# POWERSYSTEM.net
KiCad netlist of a schematic drawn in Altium Designer
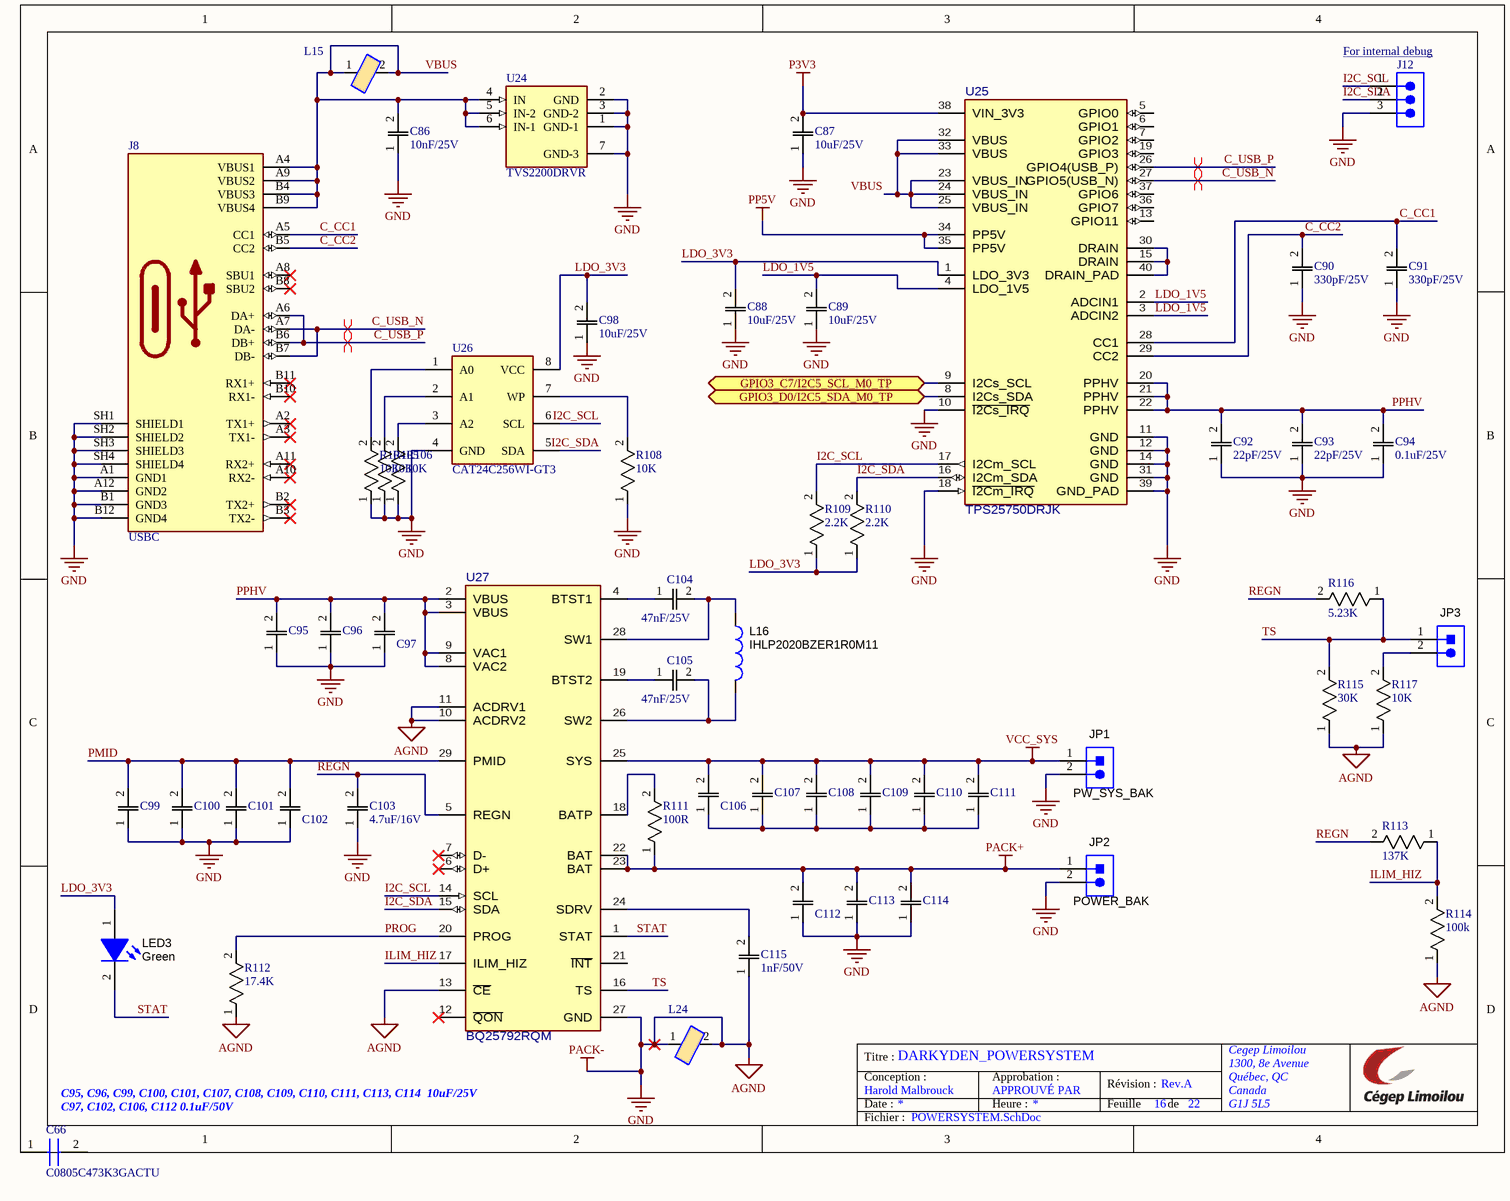
[diagram p0: POWERSYSTEM.SchDoc]

(export (version "E")
  (design (tool "Eeschema 10.0.6"))
  (components
    (comp (ref "C66")
      (value "C0805C473K3GACTU")
      (footprint "SamacSys:C0805")
      (description "Capacitor")
      (fields (field (name "MOUSER PART NUMBER") "80-C0805C473K3G"))
      (libsource (lib "*") (part "C0805C473K3GACTU"))
    )
    (comp (ref "C86")
      (value "10nF/25V")
      (footprint "C0805")
      (description "0.01uF 25V X7R 10% SMD 0805 125C Paper T/R")
      (fields
        (field (name "MANUFACTURER_PART_NUMBER") "C0805C103K3RACTU")
        (field (name "MOUSER PART NUMBER") "80-C0805C103K3R")
      )
      (libsource (lib "DARKYDEN") (part "C0805C103K3RACTU"))
    )
    (comp (ref "C87")
      (value "10uF/25V")
      (footprint "C0805")
      (description "10uF / 25 VDC, +85degC, X5R Dielec, +/-10% ¦ KEMET C0805C106K3PACTU 0805")
      (fields
        (field (name "MANUFACTURER") "KEMET")
        (field (name "MANUFACTURER PART NUMBER") "C0805C106K3PACTU")
      )
      (libsource (lib "DARKYDEN") (part "C0805C106K3PACTU"))
    )
    (comp (ref "C88")
      (value "10uF/25V")
      (footprint "C0805")
      (description "10uF / 25 VDC, +85degC, X5R Dielec, +/-10% ¦ KEMET C0805C106K3PACTU 0805")
      (fields
        (field (name "MANUFACTURER") "KEMET")
        (field (name "MANUFACTURER PART NUMBER") "C0805C106K3PACTU")
      )
      (libsource (lib "DARKYDEN") (part "C0805C106K3PACTU"))
    )
    (comp (ref "C89")
      (value "10uF/25V")
      (footprint "C0805")
      (description "10uF / 25 VDC, +85degC, X5R Dielec, +/-10% ¦ KEMET C0805C106K3PACTU 0805")
      (fields
        (field (name "MANUFACTURER") "KEMET")
        (field (name "MANUFACTURER PART NUMBER") "C0805C106K3PACTU")
      )
      (libsource (lib "DARKYDEN") (part "C0805C106K3PACTU"))
    )
    (comp (ref "C90")
      (value "330pF/25V")
      (footprint "SamacSys:C0805")
      (description "330pF 25VC0G 0805 10%")
      (fields
        (field (name "MANUFACTURER_PART_NUMBER") "C0805C331K3GACTU")
        (field (name "MOUSER PART NUMBER") "80-C0805C331K3G")
      )
      (libsource (lib "DARKYDEN") (part "C0805C331K3GACTU"))
    )
    (comp (ref "C91")
      (value "330pF/25V")
      (footprint "SamacSys:C0805")
      (description "330pF 25VC0G 0805 10%")
      (fields
        (field (name "MANUFACTURER_PART_NUMBER") "C0805C331K3GACTU")
        (field (name "MOUSER PART NUMBER") "80-C0805C331K3G")
      )
      (libsource (lib "DARKYDEN") (part "C0805C331K3GACTU"))
    )
    (comp (ref "C92")
      (value "22pF/25V")
      (footprint "c0805")
      (description "22uF/25V 20% X5R 0805")
      (fields
        (field (name "MANUFACTURER_PART_NUMBER") "CL21A226MAYNNNE")
        (field (name "MOUSER PART NUMBER") "187-CL21A226MAYNNNE")
      )
      (libsource (lib "DARKYDEN") (part "CL21A226MAYNNNE"))
    )
    (comp (ref "C93")
      (value "22pF/25V")
      (footprint "c0805")
      (description "22uF/25V 20% X5R 0805")
      (fields
        (field (name "MANUFACTURER_PART_NUMBER") "CL21A226MAYNNNE")
        (field (name "MOUSER PART NUMBER") "187-CL21A226MAYNNNE")
      )
      (libsource (lib "DARKYDEN") (part "CL21A226MAYNNNE"))
    )
    (comp (ref "C94")
      (value "0.1uF/25V")
      (footprint "c0805")
      (description "0.1uF 25V X7R 10% SMD 0805 125C Plastic T/R")
      (fields
        (field (name "MANUFACTURER") "KEMET")
        (field (name "MANUFACTURER PART NUMBER") "C0805C104K3RACTU")
      )
      (libsource (lib "DARKYDEN") (part "C0805C104K3RACTU"))
    )
    (comp (ref "C95")
      (value "10uF/25V")
      (footprint "C0805")
      (description "10uF / 25 VDC, +85degC, X5R Dielec, +/-10% ¦ KEMET C0805C106K3PACTU 0805")
      (fields
        (field (name "MANUFACTURER") "KEMET")
        (field (name "MANUFACTURER PART NUMBER") "C0805C106K3PACTU")
      )
      (libsource (lib "DARKYDEN") (part "C0805C106K3PACTU"))
    )
    (comp (ref "C96")
      (value "10uF/25V")
      (footprint "C0805")
      (description "10uF / 25 VDC, +85degC, X5R Dielec, +/-10% ¦ KEMET C0805C106K3PACTU 0805")
      (fields
        (field (name "MANUFACTURER") "KEMET")
        (field (name "MANUFACTURER PART NUMBER") "C0805C106K3PACTU")
      )
      (libsource (lib "DARKYDEN") (part "C0805C106K3PACTU"))
    )
    (comp (ref "C97")
      (value "0.1uF/50V")
      (footprint "C0805")
      (description "0.1uF/50V X7R 10% 0805 Multilayer Ceramic Capacitors Mlcc Smd/Smt Rohs")
      (fields
        (field (name "MANUFACTURER_PART_NUMBER") "C0805C104K5RACTU")
        (field (name "MOUSER PART NUMBER") "80-C0805C104K5R")
      )
      (libsource (lib "DARKYDEN") (part "C0805C104K5RACTU"))
    )
    (comp (ref "C98")
      (value "10uF/25V")
      (footprint "C0805")
      (description "10uF / 25 VDC, +85degC, X5R Dielec, +/-10% ¦ KEMET C0805C106K3PACTU 0805")
      (fields
        (field (name "MANUFACTURER") "KEMET")
        (field (name "MANUFACTURER PART NUMBER") "C0805C106K3PACTU")
      )
      (libsource (lib "DARKYDEN") (part "C0805C106K3PACTU"))
    )
    (comp (ref "C99")
      (value "10uF/25V")
      (footprint "C0805")
      (description "10uF / 25 VDC, +85degC, X5R Dielec, +/-10% ¦ KEMET C0805C106K3PACTU 0805")
      (fields
        (field (name "MANUFACTURER") "KEMET")
        (field (name "MANUFACTURER PART NUMBER") "C0805C106K3PACTU")
      )
      (libsource (lib "DARKYDEN") (part "C0805C106K3PACTU"))
    )
    (comp (ref "C100")
      (value "10uF/25V")
      (footprint "C0805")
      (description "10uF / 25 VDC, +85degC, X5R Dielec, +/-10% ¦ KEMET C0805C106K3PACTU 0805")
      (fields
        (field (name "MANUFACTURER") "KEMET")
        (field (name "MANUFACTURER PART NUMBER") "C0805C106K3PACTU")
      )
      (libsource (lib "DARKYDEN") (part "C0805C106K3PACTU"))
    )
    (comp (ref "C101")
      (value "10uF/25V")
      (footprint "C0805")
      (description "10uF / 25 VDC, +85degC, X5R Dielec, +/-10% ¦ KEMET C0805C106K3PACTU 0805")
      (fields
        (field (name "MANUFACTURER") "KEMET")
        (field (name "MANUFACTURER PART NUMBER") "C0805C106K3PACTU")
      )
      (libsource (lib "DARKYDEN") (part "C0805C106K3PACTU"))
    )
    (comp (ref "C102")
      (value "0.1uF/50V")
      (footprint "C0805")
      (description "0.1uF/50V X7R 10% 0805 Multilayer Ceramic Capacitors Mlcc Smd/Smt Rohs")
      (fields
        (field (name "MANUFACTURER_PART_NUMBER") "C0805C104K5RACTU")
        (field (name "MOUSER PART NUMBER") "80-C0805C104K5R")
      )
      (libsource (lib "DARKYDEN") (part "C0805C104K5RACTU"))
    )
    (comp (ref "C103")
      (value "4.7uF/16V")
      (footprint "C0805")
      (description "4.7 uF, 16 V, ± 10%, X7R, 0805 [2012 Metric]")
      (fields
        (field (name "MANUFACTURER_PART_NUMBER") "C0805C475K4RACTU")
        (field (name "MOUSER PART NUMBER") "80-C0805C475K4R")
      )
      (libsource (lib "DARKYDEN") (part "C0805C475K4RACTU"))
    )
    (comp (ref "C104")
      (value "47nF/25V")
      (footprint "C0805")
      (description "47nF/25V C0G 10% Pad SMD 0805 125C Extreme Low ESR T/R")
      (fields
        (field (name "MANUFACTURER_PART_NUMBER") "C0805C473K3GACTU")
        (field (name "MOUSER PART NUMBER") "80-C0805C473K3G")
      )
      (libsource (lib "DARKYDEN") (part "C0805C473K3GACTU"))
    )
    (comp (ref "C105")
      (value "47nF/25V")
      (footprint "C0805")
      (description "47nF/25V C0G 10% Pad SMD 0805 125C Extreme Low ESR T/R")
      (fields
        (field (name "MANUFACTURER_PART_NUMBER") "C0805C473K3GACTU")
        (field (name "MOUSER PART NUMBER") "80-C0805C473K3G")
      )
      (libsource (lib "DARKYDEN") (part "C0805C473K3GACTU"))
    )
    (comp (ref "C106")
      (value "0.1uF/50V")
      (footprint "C0805")
      (description "0.1uF/50V X7R 10% 0805 Multilayer Ceramic Capacitors Mlcc Smd/Smt Rohs")
      (fields
        (field (name "MANUFACTURER_PART_NUMBER") "C0805C104K5RACTU")
        (field (name "MOUSER PART NUMBER") "80-C0805C104K5R")
      )
      (libsource (lib "DARKYDEN") (part "C0805C104K5RACTU"))
    )
    (comp (ref "C107")
      (value "10uF/25V")
      (footprint "C0805")
      (description "10uF / 25 VDC, +85degC, X5R Dielec, +/-10% ¦ KEMET C0805C106K3PACTU 0805")
      (fields
        (field (name "MANUFACTURER") "KEMET")
        (field (name "MANUFACTURER PART NUMBER") "C0805C106K3PACTU")
      )
      (libsource (lib "DARKYDEN") (part "C0805C106K3PACTU"))
    )
    (comp (ref "C108")
      (value "10uF/25V")
      (footprint "C0805")
      (description "10uF / 25 VDC, +85degC, X5R Dielec, +/-10% ¦ KEMET C0805C106K3PACTU 0805")
      (fields
        (field (name "MANUFACTURER") "KEMET")
        (field (name "MANUFACTURER PART NUMBER") "C0805C106K3PACTU")
      )
      (libsource (lib "DARKYDEN") (part "C0805C106K3PACTU"))
    )
    (comp (ref "C109")
      (value "10uF/25V")
      (footprint "C0805")
      (description "10uF / 25 VDC, +85degC, X5R Dielec, +/-10% ¦ KEMET C0805C106K3PACTU 0805")
      (fields
        (field (name "MANUFACTURER") "KEMET")
        (field (name "MANUFACTURER PART NUMBER") "C0805C106K3PACTU")
      )
      (libsource (lib "DARKYDEN") (part "C0805C106K3PACTU"))
    )
    (comp (ref "C110")
      (value "10uF/25V")
      (footprint "C0805")
      (description "10uF / 25 VDC, +85degC, X5R Dielec, +/-10% ¦ KEMET C0805C106K3PACTU 0805")
      (fields
        (field (name "MANUFACTURER") "KEMET")
        (field (name "MANUFACTURER PART NUMBER") "C0805C106K3PACTU")
      )
      (libsource (lib "DARKYDEN") (part "C0805C106K3PACTU"))
    )
    (comp (ref "C111")
      (value "10uF/25V")
      (footprint "C0805")
      (description "10uF / 25 VDC, +85degC, X5R Dielec, +/-10% ¦ KEMET C0805C106K3PACTU 0805")
      (fields
        (field (name "MANUFACTURER") "KEMET")
        (field (name "MANUFACTURER PART NUMBER") "C0805C106K3PACTU")
      )
      (libsource (lib "DARKYDEN") (part "C0805C106K3PACTU"))
    )
    (comp (ref "C112")
      (value "0.1uF/50V")
      (footprint "C0805")
      (description "0.1uF/50V X7R 10% 0805 Multilayer Ceramic Capacitors Mlcc Smd/Smt Rohs")
      (fields
        (field (name "MANUFACTURER_PART_NUMBER") "C0805C104K5RACTU")
        (field (name "MOUSER PART NUMBER") "80-C0805C104K5R")
      )
      (libsource (lib "DARKYDEN") (part "C0805C104K5RACTU"))
    )
    (comp (ref "C113")
      (value "10uF/25V")
      (footprint "C0805")
      (description "10uF / 25 VDC, +85degC, X5R Dielec, +/-10% ¦ KEMET C0805C106K3PACTU 0805")
      (fields
        (field (name "MANUFACTURER") "KEMET")
        (field (name "MANUFACTURER PART NUMBER") "C0805C106K3PACTU")
      )
      (libsource (lib "DARKYDEN") (part "C0805C106K3PACTU"))
    )
    (comp (ref "C114")
      (value "10uF/25V")
      (footprint "C0805")
      (description "10uF / 25 VDC, +85degC, X5R Dielec, +/-10% ¦ KEMET C0805C106K3PACTU 0805")
      (fields
        (field (name "MANUFACTURER") "KEMET")
        (field (name "MANUFACTURER PART NUMBER") "C0805C106K3PACTU")
      )
      (libsource (lib "DARKYDEN") (part "C0805C106K3PACTU"))
    )
    (comp (ref "C115")
      (value "1nF/50V")
      (footprint "C0805")
      (description "Multilayer Ceramic Capacitor 1000 Pf 50 V ½ 10% X7R 0805 [2012 Metric]")
      (fields
        (field (name "MANUFACTURER_PART_NUMBER") "C0805C102K5RAC-TU")
        (field (name "MANUFACTURER") "KEMET")
      )
      (libsource (lib "DARKYDEN") (part "C0805C102K5RACTU"))
    )
    (comp (ref "J8")
      (value "USBC")
      (footprint "USB_C")
      (fields (field (name "MF") "Molex") (field (name "MP") "2012670005"))
      (libsource (lib "DARKYDEN") (part "USBC"))
    )
    (comp (ref "J12")
      (value "61300311121")
      (footprint "61300311121")
      (description "WR-PHD Pin Header, THT, Vertical, pitch 2.54mm, 1 Row, 3P")
      (fields (field (name "MANUFACTURER") "Wurth Elektronik"))
      (libsource (lib "Header") (part "61300311121"))
    )
    (comp (ref "JP1")
      (value "PW_SYS_BAK")
      (footprint "61300211121")
      (description "Header, 100mil, 2x1, Tin, TH")
      (fields
        (field (name "PARTNUMBER") "PEC02SAAN")
        (field (name "MANUFACTURER") "Sullins Connector Solutions")
        (field (name "PUBLISHER") "Texas Instruments")
      )
      (libsource (lib "texas_instrument_power") (part "Header_2x1"))
    )
    (comp (ref "JP2")
      (value "POWER_BAK")
      (footprint "61300211121")
      (description "Header, 100mil, 2x1, Tin, TH")
      (fields
        (field (name "PARTNUMBER") "PEC02SAAN")
        (field (name "MANUFACTURER") "Sullins Connector Solutions")
        (field (name "PUBLISHER") "Texas Instruments")
      )
      (libsource (lib "texas_instrument_power") (part "Header_2x1"))
    )
    (comp (ref "JP3")
      (value "TS")
      (footprint "61300211121")
      (description "Header, 100mil, 2x1, Tin, TH")
      (fields
        (field (name "PARTNUMBER") "PEC02SAAN")
        (field (name "MANUFACTURER") "Sullins Connector Solutions")
        (field (name "PUBLISHER") "Texas Instruments")
      )
      (libsource (lib "texas_instrument_power") (part "Header_2x1"))
    )
    (comp (ref "L15")
      (value "FBMJ2125HM210NT")
      (footprint "INDC2012X105N")
      (description "Ferrite Beads Power Chip 21Ohm 30% 100MHz 6A 0.004Ohm DCR 0805 Automotive T/R")
      (fields
        (field (name "MANUFACTURER") "Taiyo Yuden")
        (field (name "MOUSER PART NUMBER") "963-FBMJ2125HM210NT")
      )
      (libsource (lib "SamacSys") (part "FBMJ2125HM210NT"))
    )
    (comp (ref "L16")
      (value "IHLP2020BZER1R0M11")
      (footprint "IHLP-2020BZ")
      (description "Inductor, Shielded Drum Core, Powdered Iron, 1 uH, 7 A, 0.0181 ohm, SMD")
      (fields (field (name "MANUFACTURER") "Vishay-Dale") (field (name "PUBLISHER") "Texas Instruments"))
      (libsource (lib "texas_instrument_power") (part "IHLP2020BZER1R0M11"))
    )
    (comp (ref "L24")
      (value "FBMJ2125HM210NT")
      (footprint "INDC2012X105N")
      (description "Ferrite Beads Power Chip 21Ohm 30% 100MHz 6A 0.004Ohm DCR 0805 Automotive T/R")
      (fields
        (field (name "MANUFACTURER") "Taiyo Yuden")
        (field (name "MOUSER PART NUMBER") "963-FBMJ2125HM210NT")
      )
      (libsource (lib "SamacSys") (part "FBMJ2125HM210NT"))
    )
    (comp (ref "LED3")
      (value "Green")
      (footprint "LED_LTST-C190")
      (description "LED, Green, SMD")
      (fields (field (name "MANUFACTURER") "Lite-On") (field (name "PARTNUMBER") "LTST-C190GKT"))
      (libsource (lib "PD_BQ_Ref_Design") (part "LED_Gr_SMD"))
    )
    (comp (ref "R104")
      (value "10K")
      (footprint "SamacSys:RESC1608X55N")
      (description "10K Ohm 5% Res Thick Film 0603  0.1W(1/10W) ±200ppm/C Pad SMD Automotive T/R")
      (fields
        (field (name "MANUFACTURER_PART_NUMBER") "ERJ-3GEYJ103V")
        (field (name "MOUSER PART NUMBER") "667-ERJ-3GEYJ103V")
      )
      (libsource (lib "DARKYDEN") (part "ERJ-3GEYJ103V"))
    )
    (comp (ref "R105")
      (value "10K")
      (footprint "SamacSys:RESC1608X55N")
      (description "10K Ohm 5% Res Thick Film 0603  0.1W(1/10W) ±200ppm/C Pad SMD Automotive T/R")
      (fields
        (field (name "MANUFACTURER_PART_NUMBER") "ERJ-3GEYJ103V")
        (field (name "MOUSER PART NUMBER") "667-ERJ-3GEYJ103V")
      )
      (libsource (lib "DARKYDEN") (part "ERJ-3GEYJ103V"))
    )
    (comp (ref "R106")
      (value "10K")
      (footprint "SamacSys:RESC1608X55N")
      (description "10K Ohm 5% Res Thick Film 0603  0.1W(1/10W) ±200ppm/C Pad SMD Automotive T/R")
      (fields
        (field (name "MANUFACTURER_PART_NUMBER") "ERJ-3GEYJ103V")
        (field (name "MOUSER PART NUMBER") "667-ERJ-3GEYJ103V")
      )
      (libsource (lib "DARKYDEN") (part "ERJ-3GEYJ103V"))
    )
    (comp (ref "R108")
      (value "10K")
      (footprint "SamacSys:RESC1608X55N")
      (description "10K Ohm 5% Res Thick Film 0603  0.1W(1/10W) ±200ppm/C Pad SMD Automotive T/R")
      (fields
        (field (name "MANUFACTURER_PART_NUMBER") "ERJ-3GEYJ103V")
        (field (name "MOUSER PART NUMBER") "667-ERJ-3GEYJ103V")
      )
      (libsource (lib "DARKYDEN") (part "ERJ-3GEYJ103V"))
    )
    (comp (ref "R109")
      (value "2.2K")
      (footprint "SamacSys:RESC1608X55N")
      (description "2.2 kOhm, ï¿½ 5%, 100 mW, 0603 [1608 Metric], Thick Film, General Purpose")
      (fields
        (field (name "MANUFACTURER_PART_NUMBER") "ERJ-3GEYJ222V")
        (field (name "MOUSER PART NUMBER") "667-ERJ-3GEYJ222V")
      )
      (libsource (lib "DARKYDEN") (part "ERJ-3GEYJ222V"))
    )
    (comp (ref "R110")
      (value "2.2K")
      (footprint "SamacSys:RESC1608X55N")
      (description "2.2 kOhm, ï¿½ 5%, 100 mW, 0603 [1608 Metric], Thick Film, General Purpose")
      (fields
        (field (name "MANUFACTURER_PART_NUMBER") "ERJ-3GEYJ222V")
        (field (name "MOUSER PART NUMBER") "667-ERJ-3GEYJ222V")
      )
      (libsource (lib "DARKYDEN") (part "ERJ-3GEYJ222V"))
    )
    (comp (ref "R111")
      (value "100R")
      (footprint "SamacSys:RESC1608X55N")
      (description "100 Ohm 1% 1/10W 0603 ±100ppm/°C Molded SMD Punched Carrier T/R")
      (fields
        (field (name "MANUFACTURER_PART_NUMBER") "ERJ-3EKF1000V")
        (field (name "MOUSER PART NUMBER") "667-ERJ-3EKF1000V")
      )
      (libsource (lib "DARKYDEN") (part "ERJ-3EKF1000V"))
    )
    (comp (ref "R112")
      (value "17.4K")
      (footprint "SamacSys:RESC1608X55N")
      (description "17.4K Ohm 1% 1/10W +/-100ppm/ßC Molded Res Thick Film 0603  SMD Punched Carrier T/R")
      (fields
        (field (name "MANUFACTURER_PART_NUMBER") "ERJ-3EKF1742V")
        (field (name "MOUSER PART NUMBER") "667-ERJ-3EKF1742V")
      )
      (libsource (lib "DARKYDEN") (part "ERJ-3EKF1742V"))
    )
    (comp (ref "R113")
      (value "137K")
      (footprint "SamacSys:RESC1608X55N")
      (description "137K Ohm 1% 1/10W Res Thick Film 0603 ±100ppm/°C SMD Punched Carrier T/R")
      (fields
        (field (name "MANUFACTURER_PART_NUMBER") "ERJ-3EKF1373V")
        (field (name "MOUSER PART NUMBER") "667-ERJ-3EKF1373V")
      )
      (libsource (lib "DARKYDEN") (part "ERJ-3EKF1373V"))
    )
    (comp (ref "R114")
      (value "100k")
      (footprint "SamacSys:RESC1608X55N")
      (description "100K Ohm 5%  Res Thick Film 0603 1/10W +/-200ppm/ßC Molded SMD Punched Carrier T/R")
      (fields
        (field (name "MANUFACTURER_PART_NUMBER") "ERJ-3GEYJ104V")
        (field (name "MOUSER PART NUMBER") "667-ERJ-3GEYJ104V")
      )
      (libsource (lib "DARKYDEN") (part "ERJ-3GEYJ104V"))
    )
    (comp (ref "R115")
      (value "30K")
      (footprint "SamacSys:RESC1608X55N")
      (description "30K Ohm 5% 0.1W(1/10W) +/-200ppm/ßC Res Thick Film 0603  SMD Automotive T/R")
      (fields
        (field (name "MANUFACTURER_PART_NUMBER") "ERJ-3GEYJ303V")
        (field (name "MOUSER PART NUMBER") "667-ERJ-3GEYJ303V")
      )
      (libsource (lib "DARKYDEN") (part "ERJ-3GEYJ303V"))
    )
    (comp (ref "R116")
      (value "5.23K")
      (footprint "SamacSys:RESC1608X55N")
      (description "5.23K Ohm 1% 1/10W Res Thick Film 0603+/-100ppm/ßC Molded SMD Punched Carrier T/R")
      (fields
        (field (name "MANUFACTURER_PART_NUMBER") "ERJ-3EKF5231V")
        (field (name "MOUSER PART NUMBER") "667-ERJ-3EKF5231V")
      )
      (libsource (lib "DARKYDEN") (part "ERJ-3EKF5231V"))
    )
    (comp (ref "R117")
      (value "10K")
      (footprint "SamacSys:RESC1608X55N")
      (description "10K Ohm 5% Res Thick Film 0603  0.1W(1/10W) ±200ppm/C Pad SMD Automotive T/R")
      (fields
        (field (name "MANUFACTURER_PART_NUMBER") "ERJ-3GEYJ103V")
        (field (name "MOUSER PART NUMBER") "667-ERJ-3GEYJ103V")
      )
      (libsource (lib "DARKYDEN") (part "ERJ-3GEYJ103V"))
    )
    (comp (ref "U24")
      (value "TVS2200DRVR")
      (footprint "SON65P200X200X80-7N")
      (description "ESD Suppressors / TVS Diodes 22V flat-clamp surge protection device 6-WSON -40 to 125")
      (fields (field (name "MF") "Texas Instruments"))
      (libsource (lib "TVS2200") (part "TVS2200DRVR"))
    )
    (comp (ref "U25")
      (value "TPS25750DRJK")
      (footprint "RJK0038B-C01-MFG")
      (description "USB Type-C and USB PD Controller with Integrated Power Switches Optimized for Power Applications")
      (fields (field (name "MANUFACTURER") "Texas Instruments"))
      (libsource (lib "PD_BQ_Ref_Design") (part "TPS25750DRJK"))
    )
    (comp (ref "U26")
      (value "CAT24C256WI-GT3")
      (footprint "SOIC127P600X175-8N")
      (description "EEPROM Memory IC 256Kbit I2C 1 MHz 500 ns 8-SOIC")
      (fields (field (name "MOUSER PART NUMBER") "698-CAT24C256WI-GT3"))
      (libsource (lib "SamacSys") (part "CAT24C256WI-GT3"))
    )
    (comp (ref "U27")
      (value "BQ25792RQM")
      (footprint "RQM0029A-MFG")
      (description "BQ2579x HotRod")
      (fields (field (name "MANUFACTURER") "Texas Instruments"))
      (libsource (lib "PD_BQ_Ref_Design") (part "BQ2579x"))
    )
  )
  (nets
    (net (code "1") (name "/C_CC1") (class "Default")
      (node (ref "C91") (pin "2") (pinfunction "2_2") (pintype "passive"))
      (node (ref "J8") (pin "A5") (pinfunction "CC1_A5") (pintype "bidirectional"))
      (node (ref "U25") (pin "28") (pinfunction "CC1_28") (pintype "passive"))
    )
    (net (code "2") (name "/C_CC2") (class "Default")
      (node (ref "C90") (pin "2") (pinfunction "2_2") (pintype "passive"))
      (node (ref "J8") (pin "B5") (pinfunction "CC2_B5") (pintype "bidirectional"))
      (node (ref "U25") (pin "29") (pinfunction "CC2_29") (pintype "passive"))
    )
    (net (code "3") (name "/C_USB_N") (class "Default")
      (node (ref "J8") (pin "A7") (pinfunction "DA-_A7") (pintype "bidirectional"))
      (node (ref "J8") (pin "B7") (pinfunction "DB-_B7") (pintype "bidirectional"))
      (node (ref "U25") (pin "27") (pinfunction "GPIO5(USB_N)_27") (pintype "bidirectional"))
    )
    (net (code "4") (name "/C_USB_P") (class "Default")
      (node (ref "J8") (pin "A6") (pinfunction "DA+_A6") (pintype "bidirectional"))
      (node (ref "J8") (pin "B6") (pinfunction "DB+_B6") (pintype "bidirectional"))
      (node (ref "U25") (pin "26") (pinfunction "GPIO4(USB_P)_26") (pintype "bidirectional"))
    )
    (net (code "5") (name "/GPIO3_C7{slash}I2C5_SCL_M0_TP") (class "Default")
      (node (ref "U25") (pin "9") (pinfunction "I2Cs_SCL_9") (pintype "passive"))
    )
    (net (code "6") (name "/GPIO3_D0{slash}I2C5_SDA_M0_TP") (class "Default")
      (node (ref "U25") (pin "8") (pinfunction "I2Cs_SDA_8") (pintype "passive"))
    )
    (net (code "7") (name "/I2C_SCL") (class "Default")
      (node (ref "J12") (pin "1") (pinfunction "1_1") (pintype "passive"))
      (node (ref "R109") (pin "2") (pinfunction "2_2") (pintype "passive"))
      (node (ref "U25") (pin "17") (pinfunction "I2Cm_SCL_17") (pintype "output"))
      (node (ref "U26") (pin "6") (pinfunction "SCL_6") (pintype "passive"))
      (node (ref "U27") (pin "14") (pinfunction "SCL_14") (pintype "input"))
    )
    (net (code "8") (name "/I2C_SDA") (class "Default")
      (node (ref "J12") (pin "2") (pinfunction "2_2") (pintype "passive"))
      (node (ref "R110") (pin "2") (pinfunction "2_2") (pintype "passive"))
      (node (ref "U25") (pin "16") (pinfunction "I2Cm_SDA_16") (pintype "bidirectional"))
      (node (ref "U26") (pin "5") (pinfunction "SDA_5") (pintype "passive"))
      (node (ref "U27") (pin "15") (pinfunction "SDA_15") (pintype "bidirectional"))
    )
    (net (code "9") (name "/ILIM_HIZ") (class "Default")
      (node (ref "R113") (pin "1") (pinfunction "1_1") (pintype "passive"))
      (node (ref "R114") (pin "2") (pinfunction "2_2") (pintype "passive"))
      (node (ref "U27") (pin "17") (pinfunction "ILIM_HIZ_17") (pintype "passive"))
    )
    (net (code "10") (name "/LDO_1V5") (class "Default")
      (node (ref "C89") (pin "2") (pinfunction "2_2") (pintype "passive"))
      (node (ref "U25") (pin "2") (pinfunction "ADCIN1_2") (pintype "passive"))
      (node (ref "U25") (pin "3") (pinfunction "ADCIN2_3") (pintype "passive"))
      (node (ref "U25") (pin "4") (pinfunction "LDO_1V5_4") (pintype "passive"))
    )
    (net (code "11") (name "/LDO_3V3") (class "Default")
      (node (ref "C88") (pin "2") (pinfunction "2_2") (pintype "passive"))
      (node (ref "C98") (pin "2") (pinfunction "2_2") (pintype "passive"))
      (node (ref "LED3") (pin "1") (pinfunction "A_1") (pintype "passive"))
      (node (ref "R109") (pin "1") (pinfunction "1_1") (pintype "passive"))
      (node (ref "R110") (pin "1") (pinfunction "1_1") (pintype "passive"))
      (node (ref "U25") (pin "1") (pinfunction "LDO_3V3_1") (pintype "passive"))
      (node (ref "U26") (pin "8") (pinfunction "VCC_8") (pintype "passive"))
    )
    (net (code "12") (name "/PMID") (class "Default")
      (node (ref "C100") (pin "2") (pinfunction "2_2") (pintype "passive"))
      (node (ref "C101") (pin "2") (pinfunction "2_2") (pintype "passive"))
      (node (ref "C102") (pin "2") (pinfunction "2_2") (pintype "passive"))
      (node (ref "C99") (pin "2") (pinfunction "2_2") (pintype "passive"))
      (node (ref "U27") (pin "29") (pinfunction "PMID_29") (pintype "passive"))
    )
    (net (code "13") (name "/PPHV") (class "Default")
      (node (ref "C92") (pin "2") (pinfunction "2_2") (pintype "passive"))
      (node (ref "C93") (pin "2") (pinfunction "2_2") (pintype "passive"))
      (node (ref "C94") (pin "2") (pinfunction "2_2") (pintype "passive"))
      (node (ref "C95") (pin "2") (pinfunction "2_2") (pintype "passive"))
      (node (ref "C96") (pin "2") (pinfunction "2_2") (pintype "passive"))
      (node (ref "C97") (pin "2") (pinfunction "2_2") (pintype "passive"))
      (node (ref "U25") (pin "20") (pinfunction "PPHV_20") (pintype "passive"))
      (node (ref "U25") (pin "21") (pinfunction "PPHV_21") (pintype "passive"))
      (node (ref "U25") (pin "22") (pinfunction "PPHV_22") (pintype "passive"))
      (node (ref "U27") (pin "2") (pinfunction "VBUS_2") (pintype "power_in"))
      (node (ref "U27") (pin "3") (pinfunction "VBUS_3") (pintype "power_in"))
      (node (ref "U27") (pin "8") (pinfunction "VAC2_8") (pintype "power_in"))
      (node (ref "U27") (pin "9") (pinfunction "VAC1_9") (pintype "power_in"))
    )
    (net (code "14") (name "/PROG") (class "Default")
      (node (ref "R112") (pin "2") (pinfunction "2_2") (pintype "passive"))
      (node (ref "U27") (pin "20") (pinfunction "PROG_20") (pintype "passive"))
    )
    (net (code "15") (name "/REGN") (class "Default")
      (node (ref "C103") (pin "2") (pinfunction "2_2") (pintype "passive"))
      (node (ref "R113") (pin "2") (pinfunction "2_2") (pintype "passive"))
      (node (ref "R116") (pin "2") (pinfunction "2_2") (pintype "passive"))
      (node (ref "U27") (pin "5") (pinfunction "REGN_5") (pintype "passive"))
    )
    (net (code "16") (name "/STAT") (class "Default")
      (node (ref "LED3") (pin "2") (pinfunction "K_2") (pintype "passive"))
      (node (ref "U27") (pin "1") (pinfunction "STAT_1") (pintype "passive"))
    )
    (net (code "17") (name "/TS") (class "Default")
      (node (ref "JP3") (pin "1") (pinfunction "1_1") (pintype "passive"))
      (node (ref "R115") (pin "2") (pinfunction "2_2") (pintype "passive"))
      (node (ref "R116") (pin "1") (pinfunction "1_1") (pintype "passive"))
      (node (ref "U27") (pin "16") (pinfunction "TS_16") (pintype "passive"))
    )
    (net (code "18") (name "/VBUS") (class "Default")
      (node (ref "C86") (pin "2") (pinfunction "2_2") (pintype "passive"))
      (node (ref "J8") (pin "A4") (pinfunction "VBUS1_A4") (pintype "power_in"))
      (node (ref "J8") (pin "A9") (pinfunction "VBUS2_A9") (pintype "power_in"))
      (node (ref "J8") (pin "B4") (pinfunction "VBUS3_B4") (pintype "power_in"))
      (node (ref "J8") (pin "B9") (pinfunction "VBUS4_B9") (pintype "power_in"))
      (node (ref "L15") (pin "1") (pinfunction "1_1") (pintype "passive"))
      (node (ref "L15") (pin "2") (pinfunction "2_2") (pintype "passive"))
      (node (ref "U24") (pin "4") (pinfunction "IN_4") (pintype "input"))
      (node (ref "U24") (pin "5") (pinfunction "IN-2_5") (pintype "input"))
      (node (ref "U24") (pin "6") (pinfunction "IN-1_6") (pintype "input"))
      (node (ref "U25") (pin "23") (pinfunction "VBUS_IN_23") (pintype "power_in"))
      (node (ref "U25") (pin "24") (pinfunction "VBUS_IN_24") (pintype "power_in"))
      (node (ref "U25") (pin "25") (pinfunction "VBUS_IN_25") (pintype "power_in"))
      (node (ref "U25") (pin "32") (pinfunction "VBUS_32") (pintype "power_in"))
      (node (ref "U25") (pin "33") (pinfunction "VBUS_33") (pintype "power_in"))
    )
    (net (code "19") (name "AGND") (class "Default")
      (node (ref "C100") (pin "1") (pinfunction "1_1") (pintype "passive"))
      (node (ref "C101") (pin "1") (pinfunction "1_1") (pintype "passive"))
      (node (ref "C102") (pin "1") (pinfunction "1_1") (pintype "passive"))
      (node (ref "C103") (pin "1") (pinfunction "1_1") (pintype "passive"))
      (node (ref "C112") (pin "1") (pinfunction "1_1") (pintype "passive"))
      (node (ref "C113") (pin "1") (pinfunction "1_1") (pintype "passive"))
      (node (ref "C114") (pin "1") (pinfunction "1_1") (pintype "passive"))
      (node (ref "C115") (pin "1") (pinfunction "1_1") (pintype "passive"))
      (node (ref "C86") (pin "1") (pinfunction "1_1") (pintype "passive"))
      (node (ref "C87") (pin "1") (pinfunction "1_1") (pintype "passive"))
      (node (ref "C88") (pin "1") (pinfunction "1_1") (pintype "passive"))
      (node (ref "C89") (pin "1") (pinfunction "1_1") (pintype "passive"))
      (node (ref "C90") (pin "1") (pinfunction "1_1") (pintype "passive"))
      (node (ref "C91") (pin "1") (pinfunction "1_1") (pintype "passive"))
      (node (ref "C92") (pin "1") (pinfunction "1_1") (pintype "passive"))
      (node (ref "C93") (pin "1") (pinfunction "1_1") (pintype "passive"))
      (node (ref "C94") (pin "1") (pinfunction "1_1") (pintype "passive"))
      (node (ref "C95") (pin "1") (pinfunction "1_1") (pintype "passive"))
      (node (ref "C96") (pin "1") (pinfunction "1_1") (pintype "passive"))
      (node (ref "C97") (pin "1") (pinfunction "1_1") (pintype "passive"))
      (node (ref "C98") (pin "1") (pinfunction "1_1") (pintype "passive"))
      (node (ref "C99") (pin "1") (pinfunction "1_1") (pintype "passive"))
      (node (ref "J12") (pin "3") (pinfunction "3_3") (pintype "passive"))
      (node (ref "J8") (pin "A1") (pinfunction "GND1_A1") (pintype "passive"))
      (node (ref "J8") (pin "A12") (pinfunction "GND2_A12") (pintype "passive"))
      (node (ref "J8") (pin "B1") (pinfunction "GND3_B1") (pintype "passive"))
      (node (ref "J8") (pin "B12") (pinfunction "GND4_B12") (pintype "passive"))
      (node (ref "J8") (pin "SH1") (pinfunction "SHIELD1_SH1") (pintype "passive"))
      (node (ref "J8") (pin "SH2") (pinfunction "SHIELD2_SH2") (pintype "passive"))
      (node (ref "J8") (pin "SH3") (pinfunction "SHIELD3_SH3") (pintype "passive"))
      (node (ref "J8") (pin "SH4") (pinfunction "SHIELD4_SH4") (pintype "passive"))
      (node (ref "JP1") (pin "2") (pinfunction "2_2") (pintype "passive"))
      (node (ref "JP2") (pin "2") (pinfunction "2_2") (pintype "passive"))
      (node (ref "L24") (pin "1") (pinfunction "1_1") (pintype "passive"))
      (node (ref "L24") (pin "2") (pinfunction "2_2") (pintype "passive"))
      (node (ref "R104") (pin "1") (pinfunction "1_1") (pintype "passive"))
      (node (ref "R105") (pin "1") (pinfunction "1_1") (pintype "passive"))
      (node (ref "R106") (pin "1") (pinfunction "1_1") (pintype "passive"))
      (node (ref "R108") (pin "1") (pinfunction "1_1") (pintype "passive"))
      (node (ref "R112") (pin "1") (pinfunction "1_1") (pintype "passive"))
      (node (ref "R114") (pin "1") (pinfunction "1_1") (pintype "passive"))
      (node (ref "R115") (pin "1") (pinfunction "1_1") (pintype "passive"))
      (node (ref "R117") (pin "1") (pinfunction "1_1") (pintype "passive"))
      (node (ref "U24") (pin "1") (pinfunction "GND-1_1") (pintype "passive"))
      (node (ref "U24") (pin "2") (pinfunction "GND_2") (pintype "passive"))
      (node (ref "U24") (pin "3") (pinfunction "GND-2_3") (pintype "passive"))
      (node (ref "U24") (pin "7") (pinfunction "GND-3_7") (pintype "passive"))
      (node (ref "U25") (pin "10") (pinfunction "~{I2Cs_IRQ}_10") (pintype "passive"))
      (node (ref "U25") (pin "11") (pinfunction "GND_11") (pintype "passive"))
      (node (ref "U25") (pin "12") (pinfunction "GND_12") (pintype "passive"))
      (node (ref "U25") (pin "14") (pinfunction "GND_14") (pintype "passive"))
      (node (ref "U25") (pin "18") (pinfunction "~{I2Cm_IRQ}_18") (pintype "input"))
      (node (ref "U25") (pin "31") (pinfunction "GND_31") (pintype "passive"))
      (node (ref "U25") (pin "39") (pinfunction "GND_PAD_39") (pintype "passive"))
      (node (ref "U26") (pin "4") (pinfunction "GND_4") (pintype "passive"))
      (node (ref "U27") (pin "10") (pinfunction "ACDRV2_10") (pintype "power_in"))
      (node (ref "U27") (pin "11") (pinfunction "ACDRV1_11") (pintype "power_in"))
      (node (ref "U27") (pin "13") (pinfunction "~{CE}_13") (pintype "passive"))
      (node (ref "U27") (pin "27") (pinfunction "GND_27") (pintype "power_in"))
    )
    (net (code "20") (name "Net-(C106-Pad1)") (class "Default")
      (node (ref "C106") (pin "1") (pinfunction "1_1") (pintype "passive"))
      (node (ref "C107") (pin "1") (pinfunction "1_1") (pintype "passive"))
      (node (ref "C108") (pin "1") (pinfunction "1_1") (pintype "passive"))
      (node (ref "C109") (pin "1") (pinfunction "1_1") (pintype "passive"))
      (node (ref "C110") (pin "1") (pinfunction "1_1") (pintype "passive"))
      (node (ref "C111") (pin "1") (pinfunction "1_1") (pintype "passive"))
    )
    (net (code "21") (name "Net-(JP3-Pad2)") (class "Default")
      (node (ref "JP3") (pin "2") (pinfunction "2_2") (pintype "passive"))
      (node (ref "R117") (pin "2") (pinfunction "2_2") (pintype "passive"))
    )
    (net (code "22") (name "Net-(U25-DRAIN_PAD)") (class "Default")
      (node (ref "U25") (pin "15") (pinfunction "DRAIN_15") (pintype "passive"))
      (node (ref "U25") (pin "30") (pinfunction "DRAIN_30") (pintype "passive"))
      (node (ref "U25") (pin "40") (pinfunction "DRAIN_PAD_40") (pintype "passive"))
    )
    (net (code "23") (name "Net-(U26-A0)") (class "Default")
      (node (ref "R104") (pin "2") (pinfunction "2_2") (pintype "passive"))
      (node (ref "U26") (pin "1") (pinfunction "A0_1") (pintype "passive"))
    )
    (net (code "24") (name "Net-(U26-A1)") (class "Default")
      (node (ref "R105") (pin "2") (pinfunction "2_2") (pintype "passive"))
      (node (ref "U26") (pin "2") (pinfunction "A1_2") (pintype "passive"))
    )
    (net (code "25") (name "Net-(U26-A2)") (class "Default")
      (node (ref "R106") (pin "2") (pinfunction "2_2") (pintype "passive"))
      (node (ref "U26") (pin "3") (pinfunction "A2_3") (pintype "passive"))
    )
    (net (code "26") (name "Net-(U26-WP)") (class "Default")
      (node (ref "R108") (pin "2") (pinfunction "2_2") (pintype "passive"))
      (node (ref "U26") (pin "7") (pinfunction "WP_7") (pintype "passive"))
    )
    (net (code "27") (name "Net-(U27-BATP)") (class "Default")
      (node (ref "R111") (pin "2") (pinfunction "2_2") (pintype "passive"))
      (node (ref "U27") (pin "18") (pinfunction "BATP_18") (pintype "passive"))
    )
    (net (code "28") (name "Net-(U27-BTST1)") (class "Default")
      (node (ref "C104") (pin "1") (pinfunction "1_1") (pintype "passive"))
      (node (ref "U27") (pin "4") (pinfunction "BTST1_4") (pintype "passive"))
    )
    (net (code "29") (name "Net-(U27-BTST2)") (class "Default")
      (node (ref "C105") (pin "1") (pinfunction "1_1") (pintype "passive"))
      (node (ref "U27") (pin "19") (pinfunction "BTST2_19") (pintype "passive"))
    )
    (net (code "30") (name "Net-(U27-SDRV)") (class "Default")
      (node (ref "C115") (pin "2") (pinfunction "2_2") (pintype "passive"))
      (node (ref "U27") (pin "24") (pinfunction "SDRV_24") (pintype "passive"))
    )
    (net (code "31") (name "Net-(U27-SW1)") (class "Default")
      (node (ref "C104") (pin "2") (pinfunction "2_2") (pintype "passive"))
      (node (ref "L16") (pin "1") (pinfunction "1_1") (pintype "passive"))
      (node (ref "U27") (pin "28") (pinfunction "SW1_28") (pintype "passive"))
    )
    (net (code "32") (name "Net-(U27-SW2)") (class "Default")
      (node (ref "C105") (pin "2") (pinfunction "2_2") (pintype "passive"))
      (node (ref "L16") (pin "2") (pinfunction "2_2") (pintype "passive"))
      (node (ref "U27") (pin "26") (pinfunction "SW2_26") (pintype "passive"))
    )
    (net (code "33") (name "P3V3") (class "Default")
      (node (ref "C87") (pin "2") (pinfunction "2_2") (pintype "passive"))
      (node (ref "U25") (pin "38") (pinfunction "VIN_3V3_38") (pintype "power_in"))
    )
    (net (code "34") (name "PACK+") (class "Default")
      (node (ref "C112") (pin "2") (pinfunction "2_2") (pintype "passive"))
      (node (ref "C113") (pin "2") (pinfunction "2_2") (pintype "passive"))
      (node (ref "C114") (pin "2") (pinfunction "2_2") (pintype "passive"))
      (node (ref "JP2") (pin "1") (pinfunction "1_1") (pintype "passive"))
      (node (ref "R111") (pin "1") (pinfunction "1_1") (pintype "passive"))
      (node (ref "U27") (pin "22") (pinfunction "BAT_22") (pintype "passive"))
      (node (ref "U27") (pin "23") (pinfunction "BAT_23") (pintype "passive"))
    )
    (net (code "35") (name "PP5V") (class "Default")
      (node (ref "U25") (pin "34") (pinfunction "PP5V_34") (pintype "power_in"))
      (node (ref "U25") (pin "35") (pinfunction "PP5V_35") (pintype "power_in"))
    )
    (net (code "36") (name "VCC_SYS") (class "Default")
      (node (ref "C106") (pin "2") (pinfunction "2_2") (pintype "passive"))
      (node (ref "C107") (pin "2") (pinfunction "2_2") (pintype "passive"))
      (node (ref "C108") (pin "2") (pinfunction "2_2") (pintype "passive"))
      (node (ref "C109") (pin "2") (pinfunction "2_2") (pintype "passive"))
      (node (ref "C110") (pin "2") (pinfunction "2_2") (pintype "passive"))
      (node (ref "C111") (pin "2") (pinfunction "2_2") (pintype "passive"))
      (node (ref "JP1") (pin "1") (pinfunction "1_1") (pintype "passive"))
      (node (ref "U27") (pin "25") (pinfunction "SYS_25") (pintype "passive"))
    )
    (net (code "37") (name "unconnected-(C66-Pad1)") (class "Default")
      (node (ref "C66") (pin "1") (pinfunction "1_1") (pintype "passive"))
    )
    (net (code "38") (name "unconnected-(C66-Pad2)") (class "Default")
      (node (ref "C66") (pin "2") (pinfunction "2_2") (pintype "passive"))
    )
    (net (code "39") (name "unconnected-(J8-RX1+-PadB11)") (class "Default")
      (node (ref "J8") (pin "B11") (pinfunction "RX1+_B11") (pintype "input+no_connect"))
    )
    (net (code "40") (name "unconnected-(J8-RX1--PadB10)") (class "Default")
      (node (ref "J8") (pin "B10") (pinfunction "RX1-_B10") (pintype "input+no_connect"))
    )
    (net (code "41") (name "unconnected-(J8-RX2+-PadA11)") (class "Default")
      (node (ref "J8") (pin "A11") (pinfunction "RX2+_A11") (pintype "input+no_connect"))
    )
    (net (code "42") (name "unconnected-(J8-RX2--PadA10)") (class "Default")
      (node (ref "J8") (pin "A10") (pinfunction "RX2-_A10") (pintype "input+no_connect"))
    )
    (net (code "43") (name "unconnected-(J8-SBU1-PadA8)") (class "Default")
      (node (ref "J8") (pin "A8") (pinfunction "SBU1_A8") (pintype "bidirectional+no_connect"))
    )
    (net (code "44") (name "unconnected-(J8-SBU2-PadB8)") (class "Default")
      (node (ref "J8") (pin "B8") (pinfunction "SBU2_B8") (pintype "bidirectional+no_connect"))
    )
    (net (code "45") (name "unconnected-(J8-TX1+-PadA2)") (class "Default")
      (node (ref "J8") (pin "A2") (pinfunction "TX1+_A2") (pintype "output+no_connect"))
    )
    (net (code "46") (name "unconnected-(J8-TX1--PadA3)") (class "Default")
      (node (ref "J8") (pin "A3") (pinfunction "TX1-_A3") (pintype "output+no_connect"))
    )
    (net (code "47") (name "unconnected-(J8-TX2+-PadB2)") (class "Default")
      (node (ref "J8") (pin "B2") (pinfunction "TX2+_B2") (pintype "output+no_connect"))
    )
    (net (code "48") (name "unconnected-(J8-TX2--PadB3)") (class "Default")
      (node (ref "J8") (pin "B3") (pinfunction "TX2-_B3") (pintype "output+no_connect"))
    )
    (net (code "49") (name "unconnected-(U25-GPIO0-Pad5)") (class "Default")
      (node (ref "U25") (pin "5") (pinfunction "GPIO0_5") (pintype "bidirectional"))
    )
    (net (code "50") (name "unconnected-(U25-GPIO1-Pad6)") (class "Default")
      (node (ref "U25") (pin "6") (pinfunction "GPIO1_6") (pintype "bidirectional"))
    )
    (net (code "51") (name "unconnected-(U25-GPIO2-Pad7)") (class "Default")
      (node (ref "U25") (pin "7") (pinfunction "GPIO2_7") (pintype "bidirectional"))
    )
    (net (code "52") (name "unconnected-(U25-GPIO3-Pad19)") (class "Default")
      (node (ref "U25") (pin "19") (pinfunction "GPIO3_19") (pintype "bidirectional"))
    )
    (net (code "53") (name "unconnected-(U25-GPIO6-Pad37)") (class "Default")
      (node (ref "U25") (pin "37") (pinfunction "GPIO6_37") (pintype "bidirectional"))
    )
    (net (code "54") (name "unconnected-(U25-GPIO7-Pad36)") (class "Default")
      (node (ref "U25") (pin "36") (pinfunction "GPIO7_36") (pintype "bidirectional"))
    )
    (net (code "55") (name "unconnected-(U25-GPIO11-Pad13)") (class "Default")
      (node (ref "U25") (pin "13") (pinfunction "GPIO11_13") (pintype "bidirectional"))
    )
    (net (code "56") (name "unconnected-(U27-D+-Pad6)") (class "Default")
      (node (ref "U27") (pin "6") (pinfunction "D+_6") (pintype "bidirectional+no_connect"))
    )
    (net (code "57") (name "unconnected-(U27-D--Pad7)") (class "Default")
      (node (ref "U27") (pin "7") (pinfunction "D-_7") (pintype "bidirectional+no_connect"))
    )
    (net (code "58") (name "unconnected-(U27-~{INT}-Pad21)") (class "Default")
      (node (ref "U27") (pin "21") (pinfunction "~{INT}_21") (pintype "passive"))
    )
    (net (code "59") (name "unconnected-(U27-~{QON}-Pad12)") (class "Default")
      (node (ref "U27") (pin "12") (pinfunction "~{QON}_12") (pintype "passive+no_connect"))
    )
  )
)
